# EmonTxShieldV2_5.net
KiCad netlist of a schematic drawn in EAGLE
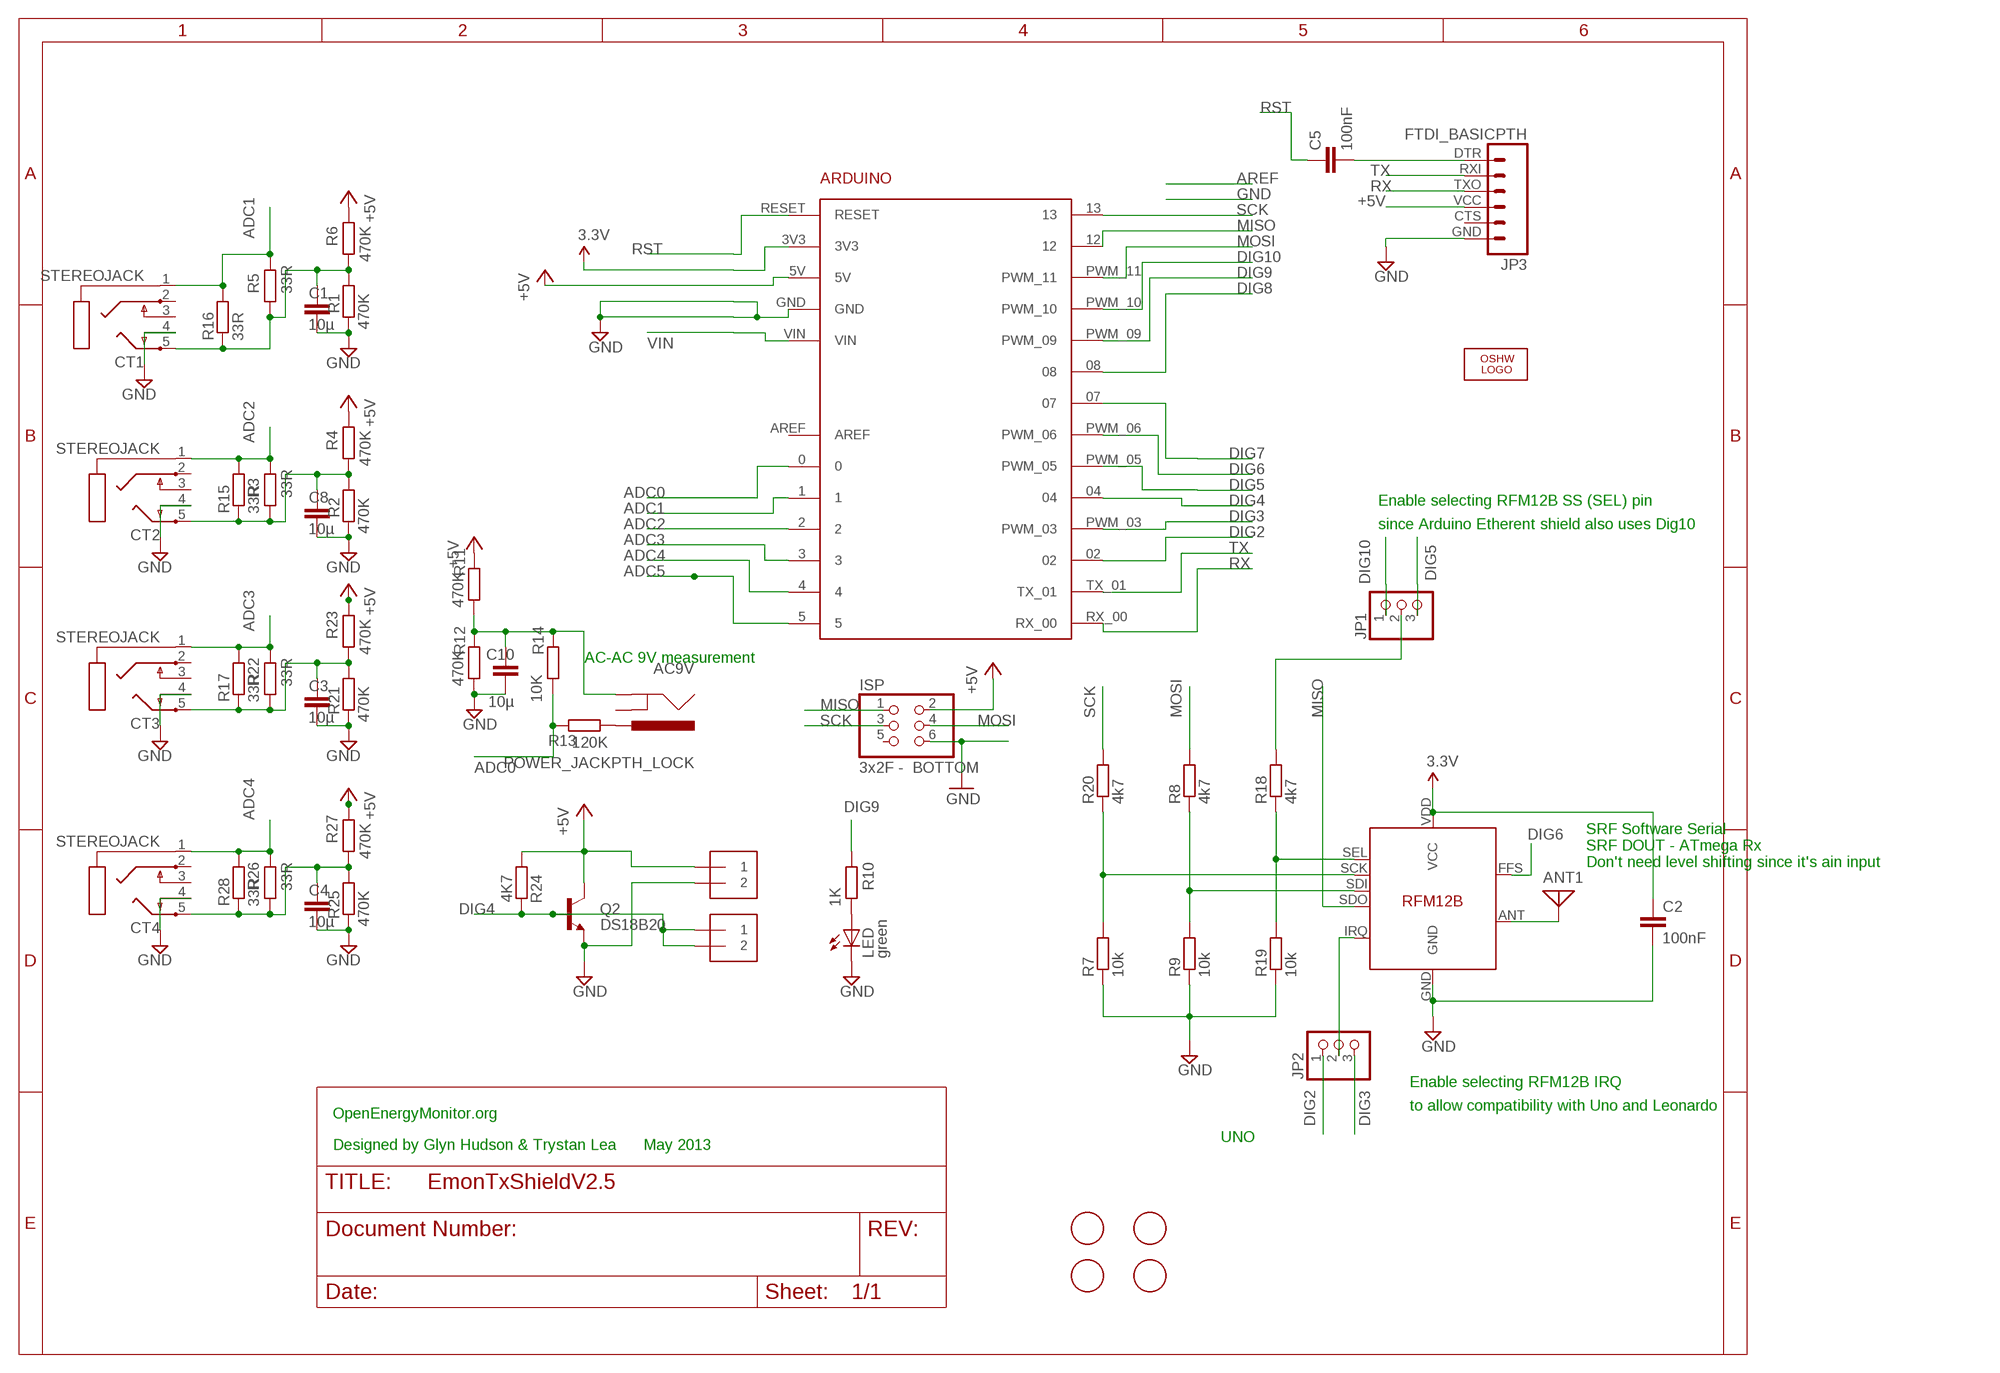
[diagram p0: schematic, sheet 1]

(export (version "E")
  (design (tool "Eeschema 10.0.6"))
  (components
    (comp (ref "AC9V")
      (value "POWER_JACKPTH_LOCK")
      (footprint "eagle-import:POWER_JACK_PTH_LOCK")
      (libsource (lib "eagle-import") (part "POWER_JACKPTH_LOCK"))
    )
    (comp (ref "ANT1")
      (value "ANTENNA")
      (footprint "eagle-import:PAD-01")
      (libsource (lib "eagle-import") (part "ANTENNA"))
    )
    (comp (ref "ARDUINO1")
      (value "ARDUINO2")
      (footprint "eagle-import:ARDUINO2")
      (libsource (lib "eagle-import") (part "ARDUINO2"))
    )
    (comp (ref "C1")
      (value "10µ")
      (footprint "eagle-import:C0603")
      (libsource (lib "eagle-import") (part "C-EUC0603"))
    )
    (comp (ref "C2")
      (value "100nF")
      (footprint "eagle-import:C0603")
      (libsource (lib "eagle-import") (part "C-EUC0603"))
    )
    (comp (ref "C3")
      (value "10µ")
      (footprint "eagle-import:C0603")
      (libsource (lib "eagle-import") (part "C-EUC0603"))
    )
    (comp (ref "C4")
      (value "10µ")
      (footprint "eagle-import:C0603")
      (libsource (lib "eagle-import") (part "C-EUC0603"))
    )
    (comp (ref "C5")
      (value "100nF")
      (footprint "eagle-import:C0603")
      (libsource (lib "eagle-import") (part "C-EUC0603"))
    )
    (comp (ref "C8")
      (value "10µ")
      (footprint "eagle-import:C0603")
      (libsource (lib "eagle-import") (part "C-EUC0603"))
    )
    (comp (ref "C10")
      (value "10µ")
      (footprint "eagle-import:C0603")
      (libsource (lib "eagle-import") (part "C-EUC0603"))
    )
    (comp (ref "CT1")
      (value "STEREOJACK")
      (footprint "eagle-import:STX3100")
      (libsource (lib "eagle-import") (part "STEREOJACK"))
    )
    (comp (ref "CT2")
      (value "STEREOJACK")
      (footprint "eagle-import:STX3100")
      (libsource (lib "eagle-import") (part "STEREOJACK"))
    )
    (comp (ref "CT3")
      (value "STEREOJACK")
      (footprint "eagle-import:STX3100")
      (libsource (lib "eagle-import") (part "STEREOJACK"))
    )
    (comp (ref "CT4")
      (value "STEREOJACK")
      (footprint "eagle-import:STX3100")
      (libsource (lib "eagle-import") (part "STEREOJACK"))
    )
    (comp (ref "ISP")
      (value "3x2F - BOTTOM")
      (footprint "eagle-import:2X03")
      (libsource (lib "eagle-import") (part "PINHD-2X3"))
    )
    (comp (ref "J1")
      (value "1X2-3.5MM")
      (footprint "eagle-import:1X2-3.5MM")
      (libsource (lib "eagle-import") (part "1X2-3.5MM"))
    )
    (comp (ref "J2")
      (value "1X2-3.5MM")
      (footprint "eagle-import:1X2-3.5MM")
      (libsource (lib "eagle-import") (part "1X2-3.5MM"))
    )
    (comp (ref "JP1")
      (value "PINHD-1X3")
      (footprint "eagle-import:1X03")
      (libsource (lib "eagle-import") (part "PINHD-1X3"))
    )
    (comp (ref "JP2")
      (value "PINHD-1X3")
      (footprint "eagle-import:1X03")
      (libsource (lib "eagle-import") (part "PINHD-1X3"))
    )
    (comp (ref "JP3")
      (value "FTDI_BASICPTH")
      (footprint "eagle-import:FTDI_BASIC")
      (libsource (lib "eagle-import") (part "FTDI_BASICPTH"))
    )
    (comp (ref "LED")
      (value "green")
      (footprint "eagle-import:CHIPLED_0805")
      (libsource (lib "eagle-import") (part "LEDCHIPLED_0805"))
    )
    (comp (ref "LOGO1")
      (value "OSHW_LOGO_10MILX0200-NT")
      (footprint "eagle-import:OSHW_10X200_NOTEXT")
      (libsource (lib "eagle-import") (part "OSHW_LOGO_10MILX0200-NT"))
    )
    (comp (ref "Q2")
      (value "DS18B20")
      (footprint "eagle-import:TO-92")
      (libsource (lib "eagle-import") (part "TRANSISTOR_NPNTO92"))
    )
    (comp (ref "R1")
      (value "470K")
      (footprint "eagle-import:R0603")
      (libsource (lib "eagle-import") (part "R-EU_R0603"))
    )
    (comp (ref "R2")
      (value "470K")
      (footprint "eagle-import:R0603")
      (libsource (lib "eagle-import") (part "R-EU_R0603"))
    )
    (comp (ref "R3")
      (value "33R")
      (footprint "eagle-import:0204_7")
      (libsource (lib "eagle-import") (part "R-EU_0204/7"))
    )
    (comp (ref "R4")
      (value "470K")
      (footprint "eagle-import:R0603")
      (libsource (lib "eagle-import") (part "R-EU_R0603"))
    )
    (comp (ref "R5")
      (value "33R")
      (footprint "eagle-import:0204_7")
      (libsource (lib "eagle-import") (part "R-EU_0204/7"))
    )
    (comp (ref "R6")
      (value "470K")
      (footprint "eagle-import:R0603")
      (libsource (lib "eagle-import") (part "R-EU_R0603"))
    )
    (comp (ref "R7")
      (value "10k")
      (footprint "eagle-import:R0603")
      (libsource (lib "eagle-import") (part "R-EU_R0603"))
    )
    (comp (ref "R8")
      (value "4k7")
      (footprint "eagle-import:R0603")
      (libsource (lib "eagle-import") (part "R-EU_R0603"))
    )
    (comp (ref "R9")
      (value "10k")
      (footprint "eagle-import:R0603")
      (libsource (lib "eagle-import") (part "R-EU_R0603"))
    )
    (comp (ref "R10")
      (value "1K")
      (footprint "eagle-import:R0603")
      (libsource (lib "eagle-import") (part "R-EU_R0603"))
    )
    (comp (ref "R11")
      (value "470K")
      (footprint "eagle-import:R0603")
      (libsource (lib "eagle-import") (part "R-EU_R0603"))
    )
    (comp (ref "R12")
      (value "470K")
      (footprint "eagle-import:R0603")
      (libsource (lib "eagle-import") (part "R-EU_R0603"))
    )
    (comp (ref "R13")
      (value "120K")
      (footprint "eagle-import:R0603")
      (libsource (lib "eagle-import") (part "R-EU_R0603"))
    )
    (comp (ref "R14")
      (value "10K")
      (footprint "eagle-import:R0603")
      (libsource (lib "eagle-import") (part "R-EU_R0603"))
    )
    (comp (ref "R15")
      (value "33R")
      (footprint "eagle-import:R1206")
      (libsource (lib "eagle-import") (part "R-EU_R1206"))
    )
    (comp (ref "R16")
      (value "33R")
      (footprint "eagle-import:R1206")
      (libsource (lib "eagle-import") (part "R-EU_R1206"))
    )
    (comp (ref "R17")
      (value "33R")
      (footprint "eagle-import:R1206")
      (libsource (lib "eagle-import") (part "R-EU_R1206"))
    )
    (comp (ref "R18")
      (value "4k7")
      (footprint "eagle-import:R0603")
      (libsource (lib "eagle-import") (part "R-EU_R0603"))
    )
    (comp (ref "R19")
      (value "10k")
      (footprint "eagle-import:R0603")
      (libsource (lib "eagle-import") (part "R-EU_R0603"))
    )
    (comp (ref "R20")
      (value "4k7")
      (footprint "eagle-import:R0603")
      (libsource (lib "eagle-import") (part "R-EU_R0603"))
    )
    (comp (ref "R21")
      (value "470K")
      (footprint "eagle-import:R0603")
      (libsource (lib "eagle-import") (part "R-EU_R0603"))
    )
    (comp (ref "R22")
      (value "33R")
      (footprint "eagle-import:0204_7")
      (libsource (lib "eagle-import") (part "R-EU_0204/7"))
    )
    (comp (ref "R23")
      (value "470K")
      (footprint "eagle-import:R0603")
      (libsource (lib "eagle-import") (part "R-EU_R0603"))
    )
    (comp (ref "R24")
      (value "4K7")
      (footprint "eagle-import:R0603")
      (libsource (lib "eagle-import") (part "R-EU_R0603"))
    )
    (comp (ref "R25")
      (value "470K")
      (footprint "eagle-import:R0603")
      (libsource (lib "eagle-import") (part "R-EU_R0603"))
    )
    (comp (ref "R26")
      (value "33R")
      (footprint "eagle-import:0204_7")
      (libsource (lib "eagle-import") (part "R-EU_0204/7"))
    )
    (comp (ref "R27")
      (value "470K")
      (footprint "eagle-import:R0603")
      (libsource (lib "eagle-import") (part "R-EU_R0603"))
    )
    (comp (ref "R28")
      (value "33R")
      (footprint "eagle-import:R1206")
      (libsource (lib "eagle-import") (part "R-EU_R1206"))
    )
    (comp (ref "U$1")
      (value "FIDUCIAL")
      (footprint "eagle-import:FIDUCIAL_1MM")
      (libsource (lib "eagle-import") (part "FIDUCIAL"))
    )
    (comp (ref "U$2")
      (value "RFM12B")
      (footprint "eagle-import:RFM12B")
      (libsource (lib "eagle-import") (part "RFM12B"))
    )
    (comp (ref "U$3")
      (value "FIDUCIAL")
      (footprint "eagle-import:FIDUCIAL_1MM")
      (libsource (lib "eagle-import") (part "FIDUCIAL"))
    )
    (comp (ref "U$4")
      (value "FIDUCIAL")
      (footprint "eagle-import:FIDUCIAL_1MM")
      (libsource (lib "eagle-import") (part "FIDUCIAL"))
    )
    (comp (ref "U$5")
      (value "FIDUCIAL")
      (footprint "eagle-import:FIDUCIAL_1MM")
      (libsource (lib "eagle-import") (part "FIDUCIAL"))
    )
  )
  (nets
    (net (code "1") (name "+5V") (class "Default")
      (node (ref "ARDUINO1") (pin "5V") (pinfunction "5V_5V") (pintype "bidirectional"))
      (node (ref "ISP") (pin "2") (pinfunction "2_2") (pintype "passive"))
      (node (ref "J1") (pin "1") (pinfunction "1_1") (pintype "passive"))
      (node (ref "JP3") (pin "VCC") (pinfunction "4_VCC") (pintype "passive"))
      (node (ref "Q2") (pin "3") (pinfunction "C_3") (pintype "passive"))
      (node (ref "R11") (pin "2") (pinfunction "2_2") (pintype "passive"))
      (node (ref "R23") (pin "2") (pinfunction "2_2") (pintype "passive"))
      (node (ref "R24") (pin "1") (pinfunction "1_1") (pintype "passive"))
      (node (ref "R27") (pin "2") (pinfunction "2_2") (pintype "passive"))
      (node (ref "R4") (pin "2") (pinfunction "2_2") (pintype "passive"))
      (node (ref "R6") (pin "2") (pinfunction "2_2") (pintype "passive"))
    )
    (net (code "2") (name "/ADC0") (class "Default")
      (node (ref "ARDUINO1") (pin "0") (pinfunction "0_0") (pintype "bidirectional"))
      (node (ref "R13") (pin "2") (pinfunction "2_2") (pintype "passive"))
      (node (ref "R14") (pin "1") (pinfunction "1_1") (pintype "passive"))
    )
    (net (code "3") (name "/ADC1") (class "Default")
      (node (ref "ARDUINO1") (pin "1") (pinfunction "1_1") (pintype "bidirectional"))
      (node (ref "CT1") (pin "1") (pinfunction "1_1") (pintype "passive"))
      (node (ref "R16") (pin "2") (pinfunction "2_2") (pintype "passive"))
      (node (ref "R5") (pin "2") (pinfunction "2_2") (pintype "passive"))
    )
    (net (code "4") (name "/ADC2") (class "Default")
      (node (ref "ARDUINO1") (pin "2") (pinfunction "2_2") (pintype "bidirectional"))
      (node (ref "CT2") (pin "1") (pinfunction "1_1") (pintype "passive"))
      (node (ref "R15") (pin "2") (pinfunction "2_2") (pintype "passive"))
      (node (ref "R3") (pin "2") (pinfunction "2_2") (pintype "passive"))
    )
    (net (code "5") (name "/ADC3") (class "Default")
      (node (ref "ARDUINO1") (pin "3") (pinfunction "3_3") (pintype "bidirectional"))
      (node (ref "CT3") (pin "1") (pinfunction "1_1") (pintype "passive"))
      (node (ref "R17") (pin "2") (pinfunction "2_2") (pintype "passive"))
      (node (ref "R22") (pin "2") (pinfunction "2_2") (pintype "passive"))
    )
    (net (code "6") (name "/ADC4") (class "Default")
      (node (ref "ARDUINO1") (pin "4") (pinfunction "4_4") (pintype "bidirectional"))
      (node (ref "CT4") (pin "1") (pinfunction "1_1") (pintype "passive"))
      (node (ref "R26") (pin "2") (pinfunction "2_2") (pintype "passive"))
      (node (ref "R28") (pin "2") (pinfunction "2_2") (pintype "passive"))
    )
    (net (code "7") (name "/ADC5") (class "Default")
      (node (ref "ARDUINO1") (pin "5") (pinfunction "5_5") (pintype "bidirectional"))
    )
    (net (code "9") (name "/DIG2") (class "Default")
      (node (ref "ARDUINO1") (pin "02") (pinfunction "02_02") (pintype "bidirectional"))
      (node (ref "JP2") (pin "1") (pinfunction "1_1") (pintype "passive"))
    )
    (net (code "10") (name "/DIG3") (class "Default")
      (node (ref "ARDUINO1") (pin "PWM_03") (pinfunction "PWM_03_PWM_03") (pintype "bidirectional"))
      (node (ref "JP2") (pin "3") (pinfunction "3_3") (pintype "passive"))
    )
    (net (code "11") (name "/DIG4") (class "Default")
      (node (ref "ARDUINO1") (pin "04") (pinfunction "04_04") (pintype "bidirectional"))
      (node (ref "J2") (pin "1") (pinfunction "1_1") (pintype "passive"))
      (node (ref "J2") (pin "2") (pinfunction "2_2") (pintype "passive"))
      (node (ref "Q2") (pin "2") (pinfunction "B_2") (pintype "passive"))
      (node (ref "R24") (pin "2") (pinfunction "2_2") (pintype "passive"))
    )
    (net (code "12") (name "/DIG5") (class "Default")
      (node (ref "ARDUINO1") (pin "PWM_05") (pinfunction "PWM_05_PWM_05") (pintype "bidirectional"))
      (node (ref "JP1") (pin "3") (pinfunction "3_3") (pintype "passive"))
    )
    (net (code "13") (name "/DIG6") (class "Default")
      (node (ref "ARDUINO1") (pin "PWM_06") (pinfunction "PWM_06_PWM_06") (pintype "bidirectional"))
      (node (ref "U$2") (pin "FFS") (pinfunction "FFS_FFS") (pintype "bidirectional"))
    )
    (net (code "14") (name "/DIG7") (class "Default")
      (node (ref "ARDUINO1") (pin "07") (pinfunction "07_07") (pintype "bidirectional"))
    )
    (net (code "15") (name "/DIG8") (class "Default")
      (node (ref "ARDUINO1") (pin "08") (pinfunction "08_08") (pintype "bidirectional"))
    )
    (net (code "16") (name "/DIG9") (class "Default")
      (node (ref "ARDUINO1") (pin "PWM_09") (pinfunction "PWM_09_PWM_09") (pintype "bidirectional"))
      (node (ref "R10") (pin "2") (pinfunction "2_2") (pintype "passive"))
    )
    (net (code "17") (name "/DIG10") (class "Default")
      (node (ref "ARDUINO1") (pin "PWM_10") (pinfunction "PWM_10_PWM_10") (pintype "bidirectional"))
      (node (ref "JP1") (pin "1") (pinfunction "1_1") (pintype "passive"))
    )
    (net (code "18") (name "/MISO") (class "Default")
      (node (ref "ARDUINO1") (pin "12") (pinfunction "12_12") (pintype "bidirectional"))
      (node (ref "ISP") (pin "1") (pinfunction "1_1") (pintype "passive"))
      (node (ref "U$2") (pin "SDO") (pinfunction "SDO_SDO") (pintype "output"))
    )
    (net (code "19") (name "/MOSI") (class "Default")
      (node (ref "ARDUINO1") (pin "PWM_11") (pinfunction "PWM_11_PWM_11") (pintype "bidirectional"))
      (node (ref "ISP") (pin "4") (pinfunction "4_4") (pintype "passive"))
      (node (ref "R8") (pin "2") (pinfunction "2_2") (pintype "passive"))
    )
    (net (code "20") (name "/RST") (class "Default")
      (node (ref "ARDUINO1") (pin "RESET") (pinfunction "RESET_RESET") (pintype "bidirectional"))
      (node (ref "C5") (pin "1") (pinfunction "1_1") (pintype "passive"))
    )
    (net (code "21") (name "/RX") (class "Default")
      (node (ref "ARDUINO1") (pin "RX_00") (pinfunction "RX_00_RX_00") (pintype "bidirectional"))
      (node (ref "JP3") (pin "TXO") (pinfunction "3_TXO") (pintype "passive"))
    )
    (net (code "22") (name "/SCK") (class "Default")
      (node (ref "ARDUINO1") (pin "13") (pinfunction "13_13") (pintype "bidirectional"))
      (node (ref "ISP") (pin "3") (pinfunction "3_3") (pintype "passive"))
      (node (ref "R20") (pin "2") (pinfunction "2_2") (pintype "passive"))
    )
    (net (code "23") (name "/TX") (class "Default")
      (node (ref "ARDUINO1") (pin "TX_01") (pinfunction "TX_01_TX_01") (pintype "bidirectional"))
      (node (ref "JP3") (pin "RXI") (pinfunction "2_RXI") (pintype "passive"))
    )
    (net (code "24") (name "/VIN") (class "Default")
      (node (ref "ARDUINO1") (pin "VIN") (pinfunction "VIN_VIN") (pintype "bidirectional"))
    )
    (net (code "25") (name "3.3V") (class "Default")
      (node (ref "ARDUINO1") (pin "3V3") (pinfunction "3V3_3V3") (pintype "bidirectional"))
      (node (ref "C2") (pin "1") (pinfunction "1_1") (pintype "passive"))
      (node (ref "U$2") (pin "VDD") (pinfunction "VCC_VDD") (pintype "power_in"))
    )
    (net (code "26") (name "GND") (class "Default")
      (node (ref "ARDUINO1") (pin "GND") (pinfunction "GND_GND") (pintype "bidirectional"))
      (node (ref "C1") (pin "2") (pinfunction "2_2") (pintype "passive"))
      (node (ref "C10") (pin "2") (pinfunction "2_2") (pintype "passive"))
      (node (ref "C2") (pin "2") (pinfunction "2_2") (pintype "passive"))
      (node (ref "C3") (pin "2") (pinfunction "2_2") (pintype "passive"))
      (node (ref "C4") (pin "2") (pinfunction "2_2") (pintype "passive"))
      (node (ref "C8") (pin "2") (pinfunction "2_2") (pintype "passive"))
      (node (ref "CT1") (pin "4") (pinfunction "4_4") (pintype "passive"))
      (node (ref "CT2") (pin "4") (pinfunction "4_4") (pintype "passive"))
      (node (ref "CT3") (pin "4") (pinfunction "4_4") (pintype "passive"))
      (node (ref "CT4") (pin "4") (pinfunction "4_4") (pintype "passive"))
      (node (ref "ISP") (pin "6") (pinfunction "6_6") (pintype "passive"))
      (node (ref "J1") (pin "2") (pinfunction "2_2") (pintype "passive"))
      (node (ref "JP3") (pin "GND") (pinfunction "6_GND") (pintype "passive"))
      (node (ref "LED") (pin "C") (pinfunction "C_C") (pintype "passive"))
      (node (ref "Q2") (pin "1") (pinfunction "E_1") (pintype "passive"))
      (node (ref "R1") (pin "2") (pinfunction "2_2") (pintype "passive"))
      (node (ref "R12") (pin "1") (pinfunction "1_1") (pintype "passive"))
      (node (ref "R19") (pin "1") (pinfunction "1_1") (pintype "passive"))
      (node (ref "R2") (pin "2") (pinfunction "2_2") (pintype "passive"))
      (node (ref "R21") (pin "2") (pinfunction "2_2") (pintype "passive"))
      (node (ref "R25") (pin "2") (pinfunction "2_2") (pintype "passive"))
      (node (ref "R7") (pin "1") (pinfunction "1_1") (pintype "passive"))
      (node (ref "R9") (pin "1") (pinfunction "1_1") (pintype "passive"))
      (node (ref "U$2") (pin "GND") (pinfunction "GND_GND") (pintype "power_in"))
    )
    (net (code "27") (name "Net-(AC9V-PadGND)") (class "Default")
      (node (ref "AC9V") (pin "GND") (pinfunction "GND_GND") (pintype "bidirectional"))
      (node (ref "C10") (pin "1") (pinfunction "1_1") (pintype "passive"))
      (node (ref "R11") (pin "1") (pinfunction "1_1") (pintype "passive"))
      (node (ref "R12") (pin "2") (pinfunction "2_2") (pintype "passive"))
      (node (ref "R14") (pin "2") (pinfunction "2_2") (pintype "passive"))
    )
    (net (code "28") (name "Net-(AC9V-PadPWR)") (class "Default")
      (node (ref "AC9V") (pin "PWR") (pinfunction "PWR_PWR") (pintype "bidirectional"))
      (node (ref "R13") (pin "1") (pinfunction "1_1") (pintype "passive"))
    )
    (net (code "29") (name "Net-(ANT1-Pad1)") (class "Default")
      (node (ref "ANT1") (pin "1") (pinfunction "1_1") (pintype "output"))
      (node (ref "U$2") (pin "ANT") (pinfunction "ANT_ANT") (pintype "passive"))
    )
    (net (code "30") (name "Net-(C1-Pad1)") (class "Default")
      (node (ref "C1") (pin "1") (pinfunction "1_1") (pintype "passive"))
      (node (ref "CT1") (pin "5") (pinfunction "5_5") (pintype "passive"))
      (node (ref "R1") (pin "1") (pinfunction "1_1") (pintype "passive"))
      (node (ref "R16") (pin "1") (pinfunction "1_1") (pintype "passive"))
      (node (ref "R5") (pin "1") (pinfunction "1_1") (pintype "passive"))
      (node (ref "R6") (pin "1") (pinfunction "1_1") (pintype "passive"))
    )
    (net (code "31") (name "Net-(C3-Pad1)") (class "Default")
      (node (ref "C3") (pin "1") (pinfunction "1_1") (pintype "passive"))
      (node (ref "CT3") (pin "5") (pinfunction "5_5") (pintype "passive"))
      (node (ref "R17") (pin "1") (pinfunction "1_1") (pintype "passive"))
      (node (ref "R21") (pin "1") (pinfunction "1_1") (pintype "passive"))
      (node (ref "R22") (pin "1") (pinfunction "1_1") (pintype "passive"))
      (node (ref "R23") (pin "1") (pinfunction "1_1") (pintype "passive"))
    )
    (net (code "32") (name "Net-(C4-Pad1)") (class "Default")
      (node (ref "C4") (pin "1") (pinfunction "1_1") (pintype "passive"))
      (node (ref "CT4") (pin "5") (pinfunction "5_5") (pintype "passive"))
      (node (ref "R25") (pin "1") (pinfunction "1_1") (pintype "passive"))
      (node (ref "R26") (pin "1") (pinfunction "1_1") (pintype "passive"))
      (node (ref "R27") (pin "1") (pinfunction "1_1") (pintype "passive"))
      (node (ref "R28") (pin "1") (pinfunction "1_1") (pintype "passive"))
    )
    (net (code "33") (name "Net-(C8-Pad1)") (class "Default")
      (node (ref "C8") (pin "1") (pinfunction "1_1") (pintype "passive"))
      (node (ref "CT2") (pin "5") (pinfunction "5_5") (pintype "passive"))
      (node (ref "R15") (pin "1") (pinfunction "1_1") (pintype "passive"))
      (node (ref "R2") (pin "1") (pinfunction "1_1") (pintype "passive"))
      (node (ref "R3") (pin "1") (pinfunction "1_1") (pintype "passive"))
      (node (ref "R4") (pin "1") (pinfunction "1_1") (pintype "passive"))
    )
    (net (code "34") (name "Net-(JP1-Pad2)") (class "Default")
      (node (ref "JP1") (pin "2") (pinfunction "2_2") (pintype "passive"))
      (node (ref "R18") (pin "2") (pinfunction "2_2") (pintype "passive"))
    )
    (net (code "35") (name "Net-(JP2-Pad2)") (class "Default")
      (node (ref "JP2") (pin "2") (pinfunction "2_2") (pintype "passive"))
      (node (ref "U$2") (pin "IRQ") (pinfunction "IRQ_IRQ") (pintype "open_collector"))
    )
    (net (code "36") (name "Net-(JP3-1)") (class "Default")
      (node (ref "C5") (pin "2") (pinfunction "2_2") (pintype "passive"))
      (node (ref "JP3") (pin "DTR") (pinfunction "1_DTR") (pintype "passive"))
    )
    (net (code "37") (name "Net-(LED-PadA)") (class "Default")
      (node (ref "LED") (pin "A") (pinfunction "A_A") (pintype "passive"))
      (node (ref "R10") (pin "1") (pinfunction "1_1") (pintype "passive"))
    )
    (net (code "38") (name "Net-(R8-Pad1)") (class "Default")
      (node (ref "R8") (pin "1") (pinfunction "1_1") (pintype "passive"))
      (node (ref "R9") (pin "2") (pinfunction "2_2") (pintype "passive"))
      (node (ref "U$2") (pin "SDI") (pinfunction "SDI_SDI") (pintype "input"))
    )
    (net (code "39") (name "Net-(R18-Pad1)") (class "Default")
      (node (ref "R18") (pin "1") (pinfunction "1_1") (pintype "passive"))
      (node (ref "R19") (pin "2") (pinfunction "2_2") (pintype "passive"))
      (node (ref "U$2") (pin "SEL") (pinfunction "SEL_SEL") (pintype "input"))
    )
    (net (code "40") (name "Net-(R20-Pad1)") (class "Default")
      (node (ref "R20") (pin "1") (pinfunction "1_1") (pintype "passive"))
      (node (ref "R7") (pin "2") (pinfunction "2_2") (pintype "passive"))
      (node (ref "U$2") (pin "SCK") (pinfunction "SCK_SCK") (pintype "input"))
    )
    (net (code "41") (name "unconnected-(AC9V-PadGNDBREAK)") (class "Default")
      (node (ref "AC9V") (pin "GNDBREAK") (pinfunction "GNDBREAK_GNDBREAK") (pintype "bidirectional"))
    )
    (net (code "42") (name "unconnected-(ARDUINO1-PadAREF)") (class "Default")
      (node (ref "ARDUINO1") (pin "AREF") (pinfunction "AREF_AREF") (pintype "bidirectional"))
    )
    (net (code "43") (name "unconnected-(CT1-Pad2)") (class "Default")
      (node (ref "CT1") (pin "2") (pinfunction "2_2") (pintype "passive"))
    )
    (net (code "44") (name "unconnected-(CT1-Pad3)") (class "Default")
      (node (ref "CT1") (pin "3") (pinfunction "3_3") (pintype "passive"))
    )
    (net (code "45") (name "unconnected-(CT2-Pad2)") (class "Default")
      (node (ref "CT2") (pin "2") (pinfunction "2_2") (pintype "passive"))
    )
    (net (code "46") (name "unconnected-(CT2-Pad3)") (class "Default")
      (node (ref "CT2") (pin "3") (pinfunction "3_3") (pintype "passive"))
    )
    (net (code "47") (name "unconnected-(CT3-Pad2)") (class "Default")
      (node (ref "CT3") (pin "2") (pinfunction "2_2") (pintype "passive"))
    )
    (net (code "48") (name "unconnected-(CT3-Pad3)") (class "Default")
      (node (ref "CT3") (pin "3") (pinfunction "3_3") (pintype "passive"))
    )
    (net (code "49") (name "unconnected-(CT4-Pad2)") (class "Default")
      (node (ref "CT4") (pin "2") (pinfunction "2_2") (pintype "passive"))
    )
    (net (code "50") (name "unconnected-(CT4-Pad3)") (class "Default")
      (node (ref "CT4") (pin "3") (pinfunction "3_3") (pintype "passive"))
    )
    (net (code "51") (name "unconnected-(ISP-Pad5)") (class "Default")
      (node (ref "ISP") (pin "5") (pinfunction "5_5") (pintype "passive"))
    )
    (net (code "52") (name "unconnected-(JP3-5-PadCTS)") (class "Default")
      (node (ref "JP3") (pin "CTS") (pinfunction "5_CTS") (pintype "passive"))
    )
  )
)
